# Pallette_v2_1.net
KiCad netlist of a schematic drawn in Altium Designer
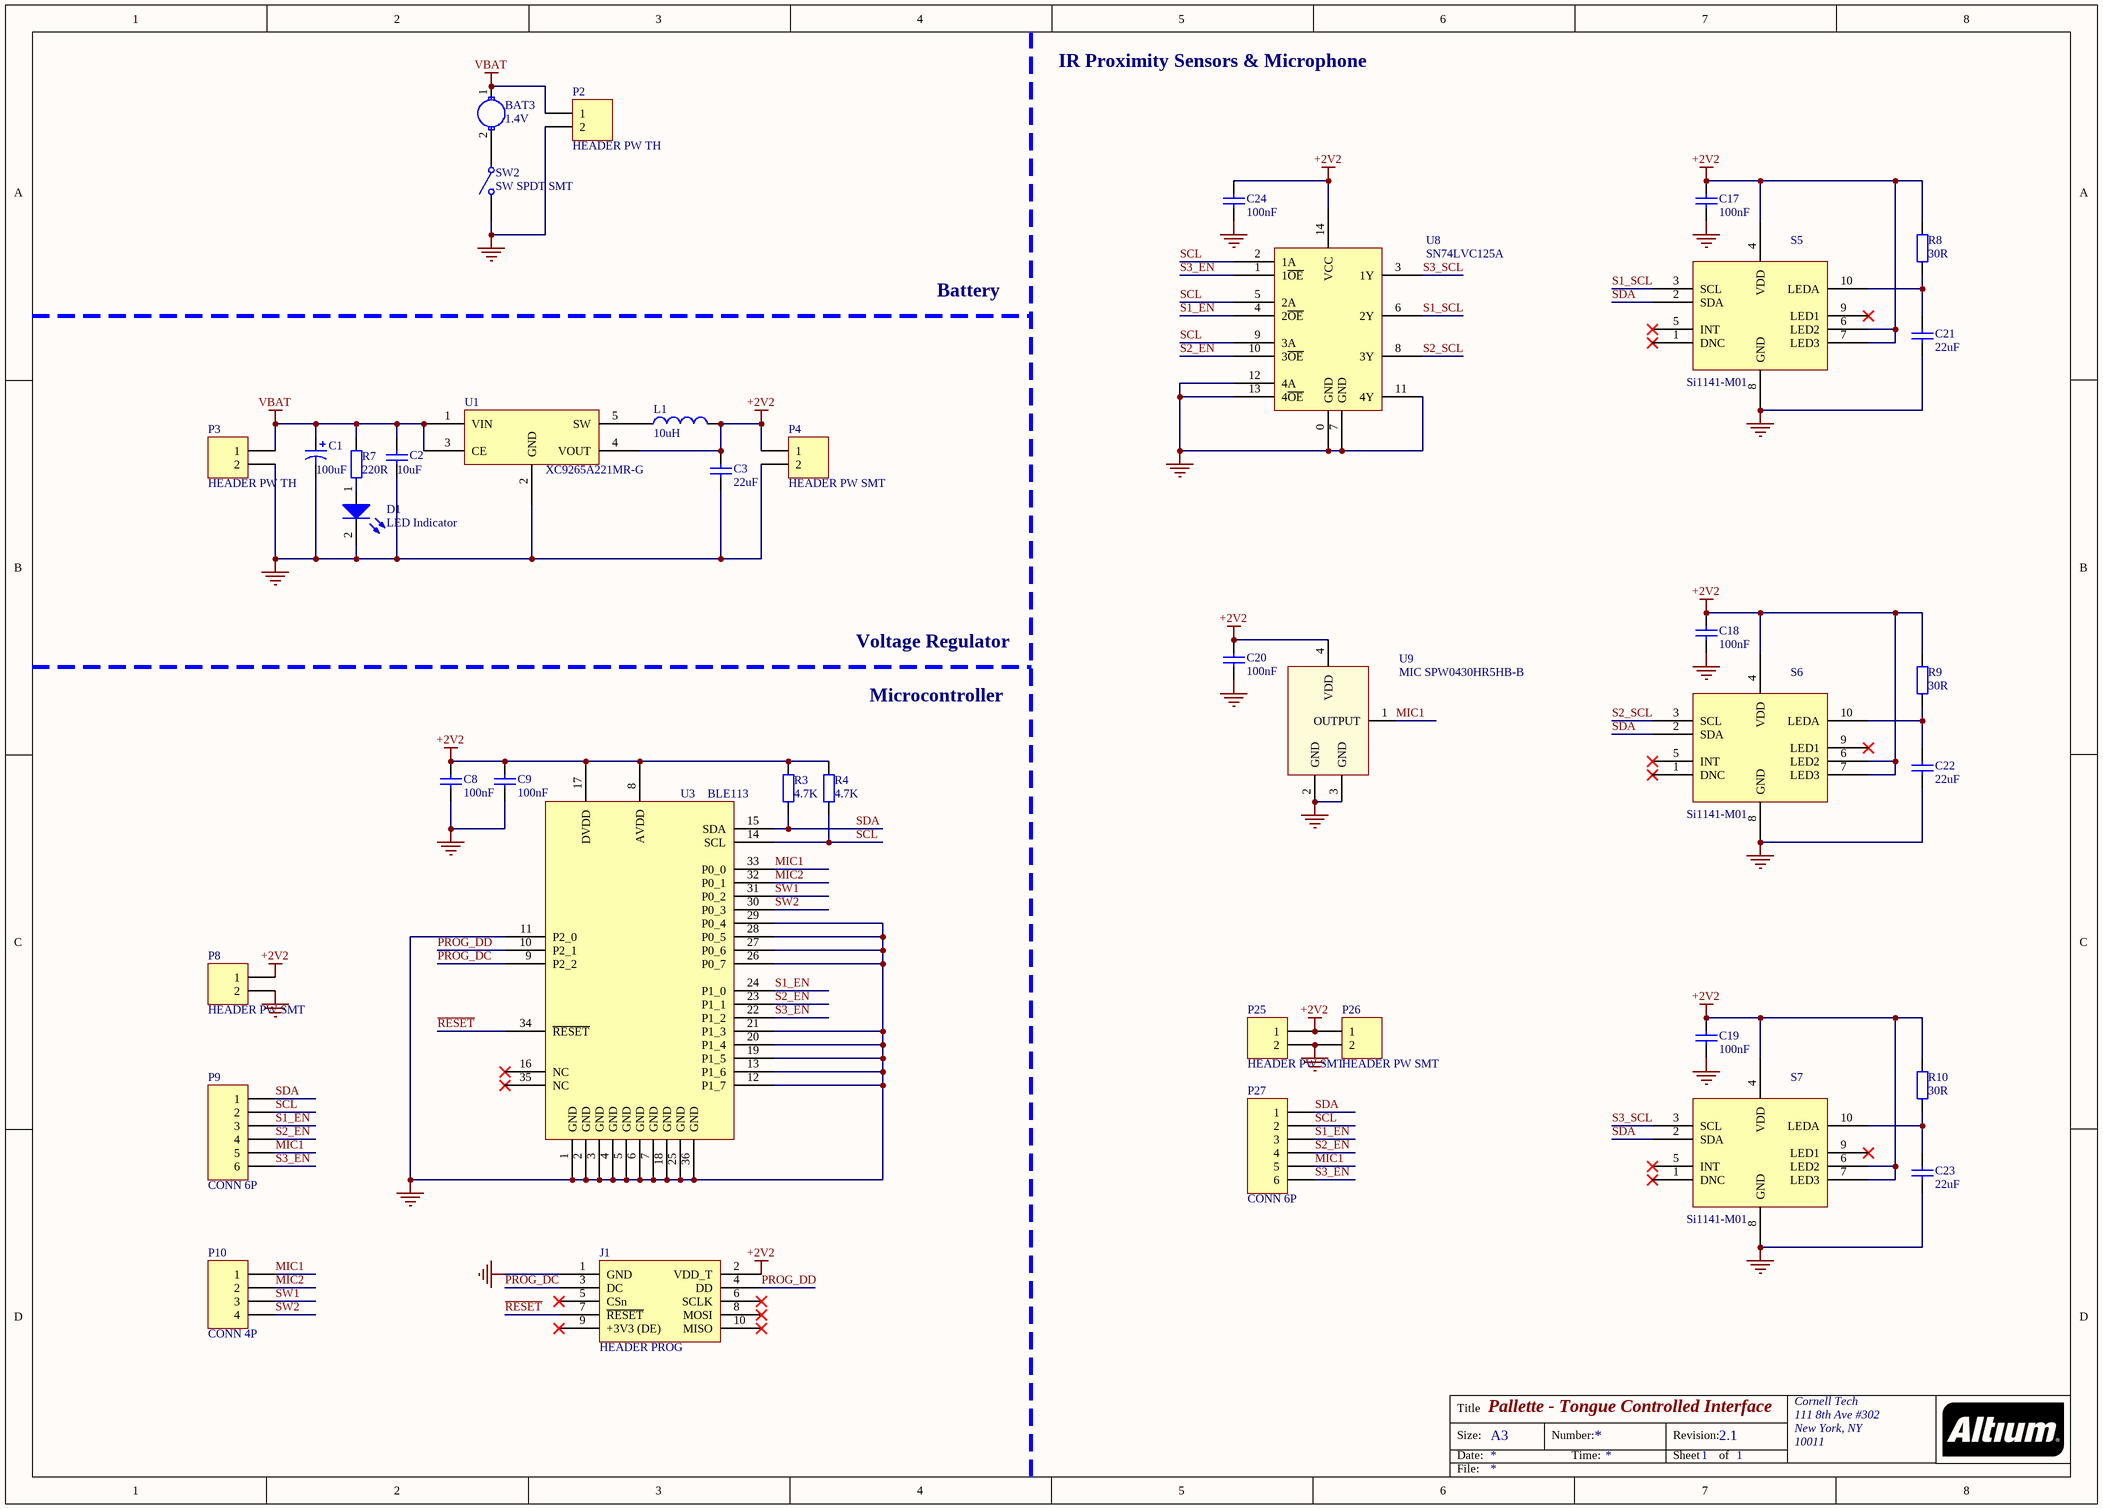
[diagram p0: Pallette v2.1.SchDoc]

(export (version "E")
  (design (tool "Eeschema 10.0.6"))
  (components
    (comp (ref "BAT3")
      (value "1.4V")
      (footprint "BAT RETAINER 13")
      (description "RETAINER COIN CELL SMD 7.9MM")
      (fields
        (field (name "DIGI-KEY PART NUMBER") "36-2988-ND")
        (field (name "MANUFACTURER") "Keystone Electronics")
      )
      (libsource (lib "Schlib") (part "BAT RETAINER 13"))
    )
    (comp (ref "C1")
      (value "100uF")
      (footprint "1411")
      (description "CAP TANT POLY 100UF 8V 1411")
      (fields
        (field (name "DIGI-KEY PART NUMBER") "P16641CT-ND")
        (field (name "MANUFACTURER") "Panasonic Electronic Components")
      )
      (libsource (lib "Schlib") (part "CAP Pol 100uF"))
    )
    (comp (ref "C2")
      (value "10uF")
      (footprint "0603")
      (description "CAP CER 10UF ±20% 10V X5R 0603")
      (fields
        (field (name "DIGI-KEY PART NUMBER") "490-12734-1-ND")
        (field (name "MANUFACTURER PART NUMBER") "GRM188R61A106MAALD")
      )
      (libsource (lib "Schlib") (part "CAP 10uF"))
    )
    (comp (ref "C3")
      (value "22uF")
      (footprint "0603")
      (description "CAP CER 22UF 6.3V X5R 0603")
      (fields
        (field (name "DIGI-KEY PART NUMBER") "490-7611-1-ND")
        (field (name "MANUFACTURER PART NUMBER") "GRM188R60J226MEA0D")
      )
      (libsource (lib "Schlib") (part "CAP 22uF"))
    )
    (comp (ref "C8")
      (value "100nF")
      (footprint "0402")
      (description "CAP CER 0.1UF 10V X5R 0402")
      (fields (field (name "DIGI-KEY PART NUMBER") "490-1318-1-ND") (field (name "MANUFACTURER") "Murata"))
      (libsource (lib "Schlib") (part "CAP 100nF"))
    )
    (comp (ref "C9")
      (value "100nF")
      (footprint "0402")
      (description "CAP CER 0.1UF 10V X5R 0402")
      (fields (field (name "DIGI-KEY PART NUMBER") "490-1318-1-ND") (field (name "MANUFACTURER") "Murata"))
      (libsource (lib "Schlib") (part "CAP 100nF"))
    )
    (comp (ref "C17")
      (value "100nF")
      (footprint "0402")
      (description "CAP CER 0.1UF 10V X5R 0402")
      (fields (field (name "DIGI-KEY PART NUMBER") "490-1318-1-ND") (field (name "MANUFACTURER") "Murata"))
      (libsource (lib "Schlib") (part "CAP 100nF"))
    )
    (comp (ref "C18")
      (value "100nF")
      (footprint "0402")
      (description "CAP CER 0.1UF 10V X5R 0402")
      (fields (field (name "DIGI-KEY PART NUMBER") "490-1318-1-ND") (field (name "MANUFACTURER") "Murata"))
      (libsource (lib "Schlib") (part "CAP 100nF"))
    )
    (comp (ref "C19")
      (value "100nF")
      (footprint "0402")
      (description "CAP CER 0.1UF 10V X5R 0402")
      (fields (field (name "DIGI-KEY PART NUMBER") "490-1318-1-ND") (field (name "MANUFACTURER") "Murata"))
      (libsource (lib "Schlib") (part "CAP 100nF"))
    )
    (comp (ref "C20")
      (value "100nF")
      (footprint "0402")
      (description "CAP CER 0.1UF 10V X5R 0402")
      (fields (field (name "DIGI-KEY PART NUMBER") "490-1318-1-ND") (field (name "MANUFACTURER") "Murata"))
      (libsource (lib "Schlib") (part "CAP 100nF"))
    )
    (comp (ref "C21")
      (value "22uF")
      (footprint "0603")
      (description "CAP CER 22UF 6.3V X5R 0603")
      (fields
        (field (name "DIGI-KEY PART NUMBER") "490-7611-1-ND")
        (field (name "MANUFACTURER PART NUMBER") "GRM188R60J226MEA0D")
      )
      (libsource (lib "Schlib") (part "CAP 22uF"))
    )
    (comp (ref "C22")
      (value "22uF")
      (footprint "0603")
      (description "CAP CER 22UF 6.3V X5R 0603")
      (fields
        (field (name "DIGI-KEY PART NUMBER") "490-7611-1-ND")
        (field (name "MANUFACTURER PART NUMBER") "GRM188R60J226MEA0D")
      )
      (libsource (lib "Schlib") (part "CAP 22uF"))
    )
    (comp (ref "C23")
      (value "22uF")
      (footprint "0603")
      (description "CAP CER 22UF 6.3V X5R 0603")
      (fields
        (field (name "DIGI-KEY PART NUMBER") "490-7611-1-ND")
        (field (name "MANUFACTURER PART NUMBER") "GRM188R60J226MEA0D")
      )
      (libsource (lib "Schlib") (part "CAP 22uF"))
    )
    (comp (ref "C24")
      (value "100nF")
      (footprint "0402")
      (description "CAP CER 0.1UF 10V X5R 0402")
      (fields (field (name "DIGI-KEY PART NUMBER") "490-1318-1-ND") (field (name "MANUFACTURER") "Murata"))
      (libsource (lib "Schlib") (part "CAP 100nF"))
    )
    (comp (ref "D1")
      (value "LED Indicator")
      (footprint "LED")
      (description "LED Red 630nm 2.2V Diffused White Lens 0603")
      (fields
        (field (name "DIGIKEY PART NUMBER") "SML-D12V1WT86CT-ND")
        (field (name "MANUFACTURER PART NUMBER") "SML-D12V1WT86")
      )
      (libsource (lib "Schlib") (part "LED Indicator"))
    )
    (comp (ref "J1")
      (value "HEADER PROG")
      (footprint "TC2050-IDC-NL")
      (description "PADS PROGRAMMING")
      (libsource (lib "Schlib") (part "HEADER PROG"))
    )
    (comp (ref "L1")
      (value "10uH")
      (footprint "0805")
      (description "FIXED IND 10UH 500MA 320 MOHM")
      (fields
        (field (name "DIGI-KEY PART NUMBER") "535-12791-1-ND")
        (field (name "MANUFACTURER") "Abracon LLC")
      )
      (libsource (lib "Schlib") (part "IND 10uH"))
    )
    (comp (ref "P2")
      (value "HEADER PW TH")
      (footprint "PORT PW TH 2P")
      (description "PADS POWER")
      (fields (field (name "PUBLISHER") "Altium Limited"))
      (libsource (lib "Schlib") (part "HEADER PW TH"))
    )
    (comp (ref "P3")
      (value "HEADER PW TH")
      (footprint "PORT PW TH 2P")
      (description "PADS POWER")
      (fields (field (name "PUBLISHER") "Altium Limited"))
      (libsource (lib "") (part "HEADER PW TH_1"))
    )
    (comp (ref "P4")
      (value "HEADER PW SMT")
      (footprint "PORT PW SMT 2P")
      (description "Connection Port")
      (fields (field (name "PUBLISHER") "Altium Limited"))
      (libsource (lib "") (part "HEADER PW SMT_1"))
    )
    (comp (ref "P8")
      (value "HEADER PW SMT")
      (footprint "PORT PW SMT 2P")
      (description "Connection Port")
      (fields (field (name "PUBLISHER") "Altium Limited"))
      (libsource (lib "Schlib") (part "HEADER PW SMT"))
    )
    (comp (ref "P9")
      (value "CONN 6P")
      (footprint "PORT CONN 6P")
      (description "Connection Port")
      (fields (field (name "PUBLISHER") "Altium Limited"))
      (libsource (lib "Schlib") (part "HEADER CONN 6P"))
    )
    (comp (ref "P10")
      (value "CONN 4P")
      (footprint "PORT CONN 4P")
      (description "Connection Port")
      (fields (field (name "PUBLISHER") "Altium Limited"))
      (libsource (lib "Schlib") (part "HEADER CONN 4P"))
    )
    (comp (ref "P25")
      (value "HEADER PW SMT")
      (footprint "PORT PW SMT 2P")
      (description "Connection Port")
      (fields (field (name "PUBLISHER") "Altium Limited"))
      (libsource (lib "Schlib") (part "HEADER PW SMT"))
    )
    (comp (ref "P26")
      (value "HEADER PW SMT")
      (footprint "PORT PW SMT 2P")
      (description "Connection Port")
      (fields (field (name "PUBLISHER") "Altium Limited"))
      (libsource (lib "") (part "HEADER PW SMT_1"))
    )
    (comp (ref "P27")
      (value "CONN 6P")
      (footprint "PORT CONN 6P")
      (description "Connection Port")
      (fields (field (name "PUBLISHER") "Altium Limited"))
      (libsource (lib "Schlib") (part "HEADER CONN 6P"))
    )
    (comp (ref "R3")
      (value "4.7K")
      (footprint "0402")
      (description "RES SMD 4.7K OHM 1% 1/16W 0402")
      (fields (field (name "DIGI-KEY PART NUMBER") "311-4.7KLRCT-ND") (field (name "MANUFACTURER") "Yageo"))
      (libsource (lib "Schlib") (part "RES 4.7K"))
    )
    (comp (ref "R4")
      (value "4.7K")
      (footprint "0402")
      (description "RES SMD 4.7K OHM 1% 1/16W 0402")
      (fields (field (name "DIGI-KEY PART NUMBER") "311-4.7KLRCT-ND") (field (name "MANUFACTURER") "Yageo"))
      (libsource (lib "Schlib") (part "RES 4.7K"))
    )
    (comp (ref "R7")
      (value "220R")
      (footprint "0603")
      (description "RES SMD 220 OHM 1% 1/10W 0603")
      (fields (field (name "DIGI-KEY PART NUMBER") "P220HCT-ND") (field (name "MANUFACTURER") "Panasonic"))
      (libsource (lib "Schlib") (part "RES 220R"))
    )
    (comp (ref "R8")
      (value "30R")
      (footprint "0402")
      (description "RES SMD 30 OHM 1% 1/16W 0402")
      (fields (field (name "DIGI-KEY PART NUMBER") "311-30LRCT-ND") (field (name "MANUFACTURER") "Yageo"))
      (libsource (lib "Schlib") (part "RES 30R"))
    )
    (comp (ref "R9")
      (value "30R")
      (footprint "0402")
      (description "RES SMD 30 OHM 1% 1/16W 0402")
      (fields (field (name "DIGI-KEY PART NUMBER") "311-30LRCT-ND") (field (name "MANUFACTURER") "Yageo"))
      (libsource (lib "Schlib") (part "RES 30R"))
    )
    (comp (ref "R10")
      (value "30R")
      (footprint "0402")
      (description "RES SMD 30 OHM 1% 1/16W 0402")
      (fields (field (name "DIGI-KEY PART NUMBER") "311-30LRCT-ND") (field (name "MANUFACTURER") "Yageo"))
      (libsource (lib "Schlib") (part "RES 30R"))
    )
    (comp (ref "S5")
      (value "Si1141-M01")
      (footprint "SI1141-M01")
      (description "SENS IR PROXIMITY AMB LT 10QFN")
      (fields
        (field (name "DIGI-KEY PART NUMBER") "336-3260-1-ND")
        (field (name "MANUFACTURER") "Silicon Labs")
      )
      (libsource (lib "Schlib") (part "Si1141-M01"))
    )
    (comp (ref "S6")
      (value "Si1141-M01")
      (footprint "SI1141-M01")
      (description "SENS IR PROXIMITY AMB LT 10QFN")
      (fields
        (field (name "DIGI-KEY PART NUMBER") "336-3260-1-ND")
        (field (name "MANUFACTURER") "Silicon Labs")
      )
      (libsource (lib "Schlib") (part "Si1141-M01"))
    )
    (comp (ref "S7")
      (value "Si1141-M01")
      (footprint "SI1141-M01")
      (description "SENS IR PROXIMITY AMB LT 10QFN")
      (fields
        (field (name "DIGI-KEY PART NUMBER") "336-3260-1-ND")
        (field (name "MANUFACTURER") "Silicon Labs")
      )
      (libsource (lib "Schlib") (part "Si1141-M01"))
    )
    (comp (ref "SW2")
      (value "SW SPDT SMT")
      (footprint "SW SPDT SMT")
      (description "SW Single-Pole Double-Throw SMT Right-Angle")
      (fields
        (field (name "DIGIKEY PART NUMBER") "401-2000-ND")
        (field (name "MANUFACTURER") "C&K Components")
      )
      (libsource (lib "Schlib") (part "SW SPDT SMT"))
    )
    (comp (ref "U1")
      (value "XC9265A221MR-G")
      (footprint "SOT-25")
      (description "IC REG BUCK 2.2V 0.2A SYNC SOT25")
      (fields
        (field (name "DIGI-KEY PART NUMBER") "893-1305-1-ND")
        (field (name "MANUFACTURER") "Torex Semiconductor Ltd")
      )
      (libsource (lib "Schlib") (part "VR XC9265A221MR-G"))
    )
    (comp (ref "U3")
      (value "BLE113")
      (footprint "BLE113-A")
      (description "MODULE BT 4.0 BLE113 OTA")
      (fields
        (field (name "MANUFACTURER") "Silicon Labs")
        (field (name "MANUFACTURER PART NUMBER") "BLE113-A-M256K")
      )
      (libsource (lib "Schlib") (part "uC BLE113"))
    )
    (comp (ref "U8")
      (value "SN74LVC125A")
      (footprint "VQFN14")
      (description "IC BUS BUFF TRI-ST QD 14VQFN")
      (fields
        (field (name "MANUFACTURER") "Texas Instruments")
        (field (name "MANUFACTURER PART NUMBER") "SN74LVC125ARGYR")
      )
      (libsource (lib "Schlib") (part "BUFF SN74LVC125A"))
    )
    (comp (ref "U9")
      (value "MIC SPW0430HR5HB-B")
      (footprint "MIC-4P")
      (description "MIC MEMS ANALOG OMNI")
      (fields (field (name "DIGI-KEY PART NUMBER") "423-1215-1-ND") (field (name "MANUFACTURER") "Knowles"))
      (libsource (lib "Schlib") (part "MIC SPW0430HR5HB-B"))
    )
  )
  (nets
    (net (code "1") (name "+2V2") (class "Default")
      (node (ref "C17") (pin "2") (pinfunction "2_2") (pintype "passive"))
      (node (ref "C18") (pin "2") (pinfunction "2_2") (pintype "passive"))
      (node (ref "C19") (pin "2") (pinfunction "2_2") (pintype "passive"))
      (node (ref "C20") (pin "1") (pinfunction "1_1") (pintype "passive"))
      (node (ref "C24") (pin "2") (pinfunction "2_2") (pintype "passive"))
      (node (ref "C3") (pin "2") (pinfunction "2_2") (pintype "passive"))
      (node (ref "C8") (pin "2") (pinfunction "2_2") (pintype "passive"))
      (node (ref "C9") (pin "2") (pinfunction "2_2") (pintype "passive"))
      (node (ref "J1") (pin "2") (pinfunction "VDD_T_2") (pintype "passive"))
      (node (ref "L1") (pin "2") (pinfunction "2_2") (pintype "passive"))
      (node (ref "P25") (pin "1") (pinfunction "1_1") (pintype "passive"))
      (node (ref "P26") (pin "1") (pinfunction "1_1") (pintype "passive"))
      (node (ref "P4") (pin "1") (pinfunction "1_1") (pintype "passive"))
      (node (ref "P8") (pin "1") (pinfunction "1_1") (pintype "passive"))
      (node (ref "R10") (pin "2") (pinfunction "2_2") (pintype "passive"))
      (node (ref "R3") (pin "2") (pinfunction "2_2") (pintype "passive"))
      (node (ref "R4") (pin "2") (pinfunction "2_2") (pintype "passive"))
      (node (ref "R8") (pin "2") (pinfunction "2_2") (pintype "passive"))
      (node (ref "R9") (pin "2") (pinfunction "2_2") (pintype "passive"))
      (node (ref "S5") (pin "4") (pinfunction "VDD_4") (pintype "passive"))
      (node (ref "S5") (pin "6") (pinfunction "LED2_6") (pintype "passive"))
      (node (ref "S5") (pin "7") (pinfunction "LED3_7") (pintype "passive"))
      (node (ref "S6") (pin "4") (pinfunction "VDD_4") (pintype "passive"))
      (node (ref "S6") (pin "6") (pinfunction "LED2_6") (pintype "passive"))
      (node (ref "S6") (pin "7") (pinfunction "LED3_7") (pintype "passive"))
      (node (ref "S7") (pin "4") (pinfunction "VDD_4") (pintype "passive"))
      (node (ref "S7") (pin "6") (pinfunction "LED2_6") (pintype "passive"))
      (node (ref "S7") (pin "7") (pinfunction "LED3_7") (pintype "passive"))
      (node (ref "U1") (pin "4") (pinfunction "VOUT_4") (pintype "passive"))
      (node (ref "U3") (pin "17") (pinfunction "DVDD_17") (pintype "passive"))
      (node (ref "U3") (pin "8") (pinfunction "AVDD_8") (pintype "passive"))
      (node (ref "U8") (pin "14") (pinfunction "VCC_14") (pintype "passive"))
      (node (ref "U9") (pin "4") (pinfunction "VDD_4") (pintype "passive"))
    )
    (net (code "2") (name "/MIC1") (class "Default")
      (node (ref "P10") (pin "1") (pinfunction "1_1") (pintype "passive"))
      (node (ref "P27") (pin "5") (pinfunction "5_5") (pintype "passive"))
      (node (ref "P9") (pin "5") (pinfunction "5_5") (pintype "passive"))
      (node (ref "U3") (pin "33") (pinfunction "P0_0_33") (pintype "passive"))
      (node (ref "U9") (pin "1") (pinfunction "OUTPUT_1") (pintype "passive"))
    )
    (net (code "3") (name "/MIC2") (class "Default")
      (node (ref "P10") (pin "2") (pinfunction "2_2") (pintype "passive"))
      (node (ref "U3") (pin "32") (pinfunction "P0_1_32") (pintype "passive"))
    )
    (net (code "4") (name "/PROG_DC") (class "Default")
      (node (ref "J1") (pin "3") (pinfunction "DC_3") (pintype "passive"))
      (node (ref "U3") (pin "9") (pinfunction "P2_2_9") (pintype "passive"))
    )
    (net (code "5") (name "/PROG_DD") (class "Default")
      (node (ref "J1") (pin "4") (pinfunction "DD_4") (pintype "passive"))
      (node (ref "U3") (pin "10") (pinfunction "P2_1_10") (pintype "passive"))
    )
    (net (code "6") (name "/S1_EN") (class "Default")
      (node (ref "P27") (pin "3") (pinfunction "3_3") (pintype "passive"))
      (node (ref "P9") (pin "3") (pinfunction "3_3") (pintype "passive"))
      (node (ref "U3") (pin "24") (pinfunction "P1_0_24") (pintype "passive"))
      (node (ref "U8") (pin "4") (pinfunction "2~{OE}_4") (pintype "passive"))
    )
    (net (code "7") (name "/S1_SCL") (class "Default")
      (node (ref "S5") (pin "3") (pinfunction "SCL_3") (pintype "passive"))
      (node (ref "U8") (pin "6") (pinfunction "2Y_6") (pintype "passive"))
    )
    (net (code "8") (name "/S2_EN") (class "Default")
      (node (ref "P27") (pin "4") (pinfunction "4_4") (pintype "passive"))
      (node (ref "P9") (pin "4") (pinfunction "4_4") (pintype "passive"))
      (node (ref "U3") (pin "23") (pinfunction "P1_1_23") (pintype "passive"))
      (node (ref "U8") (pin "10") (pinfunction "3~{OE}_10") (pintype "passive"))
    )
    (net (code "9") (name "/S2_SCL") (class "Default")
      (node (ref "S6") (pin "3") (pinfunction "SCL_3") (pintype "passive"))
      (node (ref "U8") (pin "8") (pinfunction "3Y_8") (pintype "passive"))
    )
    (net (code "10") (name "/S3_EN") (class "Default")
      (node (ref "P27") (pin "6") (pinfunction "6_6") (pintype "passive"))
      (node (ref "P9") (pin "6") (pinfunction "6_6") (pintype "passive"))
      (node (ref "U3") (pin "22") (pinfunction "P1_2_22") (pintype "passive"))
      (node (ref "U8") (pin "1") (pinfunction "1~{OE}_1") (pintype "passive"))
    )
    (net (code "11") (name "/S3_SCL") (class "Default")
      (node (ref "S7") (pin "3") (pinfunction "SCL_3") (pintype "passive"))
      (node (ref "U8") (pin "3") (pinfunction "1Y_3") (pintype "passive"))
    )
    (net (code "12") (name "/SCL") (class "Default")
      (node (ref "P27") (pin "2") (pinfunction "2_2") (pintype "passive"))
      (node (ref "P9") (pin "2") (pinfunction "2_2") (pintype "passive"))
      (node (ref "R4") (pin "1") (pinfunction "1_1") (pintype "passive"))
      (node (ref "U3") (pin "14") (pinfunction "SCL_14") (pintype "passive"))
      (node (ref "U8") (pin "2") (pinfunction "1A_2") (pintype "passive"))
      (node (ref "U8") (pin "5") (pinfunction "2A_5") (pintype "passive"))
      (node (ref "U8") (pin "9") (pinfunction "3A_9") (pintype "passive"))
    )
    (net (code "13") (name "/SDA") (class "Default")
      (node (ref "P27") (pin "1") (pinfunction "1_1") (pintype "passive"))
      (node (ref "P9") (pin "1") (pinfunction "1_1") (pintype "passive"))
      (node (ref "R3") (pin "1") (pinfunction "1_1") (pintype "passive"))
      (node (ref "S5") (pin "2") (pinfunction "SDA_2") (pintype "passive"))
      (node (ref "S6") (pin "2") (pinfunction "SDA_2") (pintype "passive"))
      (node (ref "S7") (pin "2") (pinfunction "SDA_2") (pintype "passive"))
      (node (ref "U3") (pin "15") (pinfunction "SDA_15") (pintype "passive"))
    )
    (net (code "14") (name "/SW1") (class "Default")
      (node (ref "P10") (pin "3") (pinfunction "3_3") (pintype "passive"))
      (node (ref "U3") (pin "31") (pinfunction "P0_2_31") (pintype "passive"))
    )
    (net (code "15") (name "/SW2") (class "Default")
      (node (ref "P10") (pin "4") (pinfunction "4_4") (pintype "passive"))
      (node (ref "U3") (pin "30") (pinfunction "P0_3_30") (pintype "passive"))
    )
    (net (code "16") (name "/~{RESET}") (class "Default")
      (node (ref "J1") (pin "7") (pinfunction "~{RESET}_7") (pintype "passive"))
      (node (ref "U3") (pin "34") (pinfunction "~{RESET}_34") (pintype "passive"))
    )
    (net (code "17") (name "GND") (class "Default")
      (node (ref "C1") (pin "2") (pinfunction "2_2") (pintype "passive"))
      (node (ref "C17") (pin "1") (pinfunction "1_1") (pintype "passive"))
      (node (ref "C18") (pin "1") (pinfunction "1_1") (pintype "passive"))
      (node (ref "C19") (pin "1") (pinfunction "1_1") (pintype "passive"))
      (node (ref "C2") (pin "1") (pinfunction "1_1") (pintype "passive"))
      (node (ref "C20") (pin "2") (pinfunction "2_2") (pintype "passive"))
      (node (ref "C21") (pin "1") (pinfunction "1_1") (pintype "passive"))
      (node (ref "C22") (pin "1") (pinfunction "1_1") (pintype "passive"))
      (node (ref "C23") (pin "1") (pinfunction "1_1") (pintype "passive"))
      (node (ref "C24") (pin "1") (pinfunction "1_1") (pintype "passive"))
      (node (ref "C3") (pin "1") (pinfunction "1_1") (pintype "passive"))
      (node (ref "C8") (pin "1") (pinfunction "1_1") (pintype "passive"))
      (node (ref "C9") (pin "1") (pinfunction "1_1") (pintype "passive"))
      (node (ref "D1") (pin "2") (pinfunction "K_2") (pintype "passive"))
      (node (ref "J1") (pin "1") (pinfunction "GND_1") (pintype "passive"))
      (node (ref "P2") (pin "2") (pinfunction "2_2") (pintype "passive"))
      (node (ref "P25") (pin "2") (pinfunction "2_2") (pintype "passive"))
      (node (ref "P26") (pin "2") (pinfunction "2_2") (pintype "passive"))
      (node (ref "P3") (pin "2") (pinfunction "2_2") (pintype "passive"))
      (node (ref "P4") (pin "2") (pinfunction "2_2") (pintype "passive"))
      (node (ref "P8") (pin "2") (pinfunction "2_2") (pintype "passive"))
      (node (ref "S5") (pin "8") (pinfunction "GND_8") (pintype "passive"))
      (node (ref "S6") (pin "8") (pinfunction "GND_8") (pintype "passive"))
      (node (ref "S7") (pin "8") (pinfunction "GND_8") (pintype "passive"))
      (node (ref "SW2") (pin "2") (pinfunction "NO_2") (pintype "passive"))
      (node (ref "U1") (pin "2") (pinfunction "GND_2") (pintype "passive"))
      (node (ref "U3") (pin "1") (pinfunction "GND_1") (pintype "passive"))
      (node (ref "U3") (pin "11") (pinfunction "P2_0_11") (pintype "passive"))
      (node (ref "U3") (pin "12") (pinfunction "P1_7_12") (pintype "passive"))
      (node (ref "U3") (pin "13") (pinfunction "P1_6_13") (pintype "passive"))
      (node (ref "U3") (pin "18") (pinfunction "GND_18") (pintype "passive"))
      (node (ref "U3") (pin "19") (pinfunction "P1_5_19") (pintype "passive"))
      (node (ref "U3") (pin "2") (pinfunction "GND_2") (pintype "passive"))
      (node (ref "U3") (pin "20") (pinfunction "P1_4_20") (pintype "passive"))
      (node (ref "U3") (pin "21") (pinfunction "P1_3_21") (pintype "passive"))
      (node (ref "U3") (pin "25") (pinfunction "GND_25") (pintype "passive"))
      (node (ref "U3") (pin "26") (pinfunction "P0_7_26") (pintype "passive"))
      (node (ref "U3") (pin "27") (pinfunction "P0_6_27") (pintype "passive"))
      (node (ref "U3") (pin "28") (pinfunction "P0_5_28") (pintype "passive"))
      (node (ref "U3") (pin "29") (pinfunction "P0_4_29") (pintype "passive"))
      (node (ref "U3") (pin "3") (pinfunction "GND_3") (pintype "passive"))
      (node (ref "U3") (pin "36") (pinfunction "GND_36") (pintype "passive"))
      (node (ref "U3") (pin "4") (pinfunction "GND_4") (pintype "passive"))
      (node (ref "U3") (pin "5") (pinfunction "GND_5") (pintype "passive"))
      (node (ref "U3") (pin "6") (pinfunction "GND_6") (pintype "passive"))
      (node (ref "U3") (pin "7") (pinfunction "GND_7") (pintype "passive"))
      (node (ref "U8") (pin "0") (pinfunction "GND_0") (pintype "passive"))
      (node (ref "U8") (pin "11") (pinfunction "4Y_11") (pintype "passive"))
      (node (ref "U8") (pin "12") (pinfunction "4A_12") (pintype "passive"))
      (node (ref "U8") (pin "13") (pinfunction "4~{OE}_13") (pintype "passive"))
      (node (ref "U8") (pin "7") (pinfunction "GND_7") (pintype "passive"))
      (node (ref "U9") (pin "2") (pinfunction "GND_2") (pintype "passive"))
      (node (ref "U9") (pin "3") (pinfunction "GND_3") (pintype "passive"))
    )
    (net (code "18") (name "Net-(BAT3--)") (class "Default")
      (node (ref "BAT3") (pin "2") (pinfunction "-_2") (pintype "passive"))
      (node (ref "SW2") (pin "1") (pinfunction "COMMON_1") (pintype "passive"))
    )
    (net (code "19") (name "Net-(D1-A)") (class "Default")
      (node (ref "D1") (pin "1") (pinfunction "A_1") (pintype "passive"))
      (node (ref "R7") (pin "1") (pinfunction "1_1") (pintype "passive"))
    )
    (net (code "20") (name "Net-(S5-LEDA)") (class "Default")
      (node (ref "C21") (pin "2") (pinfunction "2_2") (pintype "passive"))
      (node (ref "R8") (pin "1") (pinfunction "1_1") (pintype "passive"))
      (node (ref "S5") (pin "10") (pinfunction "LEDA_10") (pintype "passive"))
    )
    (net (code "21") (name "Net-(S6-LEDA)") (class "Default")
      (node (ref "C22") (pin "2") (pinfunction "2_2") (pintype "passive"))
      (node (ref "R9") (pin "1") (pinfunction "1_1") (pintype "passive"))
      (node (ref "S6") (pin "10") (pinfunction "LEDA_10") (pintype "passive"))
    )
    (net (code "22") (name "Net-(S7-LEDA)") (class "Default")
      (node (ref "C23") (pin "2") (pinfunction "2_2") (pintype "passive"))
      (node (ref "R10") (pin "1") (pinfunction "1_1") (pintype "passive"))
      (node (ref "S7") (pin "10") (pinfunction "LEDA_10") (pintype "passive"))
    )
    (net (code "23") (name "Net-(U1-SW)") (class "Default")
      (node (ref "L1") (pin "1") (pinfunction "1_1") (pintype "passive"))
      (node (ref "U1") (pin "5") (pinfunction "SW_5") (pintype "passive"))
    )
    (net (code "24") (name "VBAT") (class "Default")
      (node (ref "BAT3") (pin "1") (pinfunction "+_1") (pintype "passive"))
      (node (ref "C1") (pin "1") (pinfunction "1_1") (pintype "passive"))
      (node (ref "C2") (pin "2") (pinfunction "2_2") (pintype "passive"))
      (node (ref "P2") (pin "1") (pinfunction "1_1") (pintype "passive"))
      (node (ref "P3") (pin "1") (pinfunction "1_1") (pintype "passive"))
      (node (ref "R7") (pin "2") (pinfunction "2_2") (pintype "passive"))
      (node (ref "U1") (pin "1") (pinfunction "VIN_1") (pintype "passive"))
      (node (ref "U1") (pin "3") (pinfunction "CE_3") (pintype "passive"))
    )
    (net (code "25") (name "unconnected-(J1-+3V3_(DE)-Pad9)") (class "Default")
      (node (ref "J1") (pin "9") (pinfunction "+3V3_(DE)_9") (pintype "passive+no_connect"))
    )
    (net (code "26") (name "unconnected-(J1-CSn-Pad5)") (class "Default")
      (node (ref "J1") (pin "5") (pinfunction "CSn_5") (pintype "passive+no_connect"))
    )
    (net (code "27") (name "unconnected-(J1-MISO-Pad10)") (class "Default")
      (node (ref "J1") (pin "10") (pinfunction "MISO_10") (pintype "passive+no_connect"))
    )
    (net (code "28") (name "unconnected-(J1-MOSI-Pad8)") (class "Default")
      (node (ref "J1") (pin "8") (pinfunction "MOSI_8") (pintype "passive+no_connect"))
    )
    (net (code "29") (name "unconnected-(J1-SCLK-Pad6)") (class "Default")
      (node (ref "J1") (pin "6") (pinfunction "SCLK_6") (pintype "passive+no_connect"))
    )
    (net (code "30") (name "unconnected-(S5-DNC-Pad1)") (class "Default")
      (node (ref "S5") (pin "1") (pinfunction "DNC_1") (pintype "passive+no_connect"))
    )
    (net (code "31") (name "unconnected-(S5-INT-Pad5)") (class "Default")
      (node (ref "S5") (pin "5") (pinfunction "INT_5") (pintype "passive+no_connect"))
    )
    (net (code "32") (name "unconnected-(S5-LED1-Pad9)") (class "Default")
      (node (ref "S5") (pin "9") (pinfunction "LED1_9") (pintype "passive+no_connect"))
    )
    (net (code "33") (name "unconnected-(S6-DNC-Pad1)") (class "Default")
      (node (ref "S6") (pin "1") (pinfunction "DNC_1") (pintype "passive+no_connect"))
    )
    (net (code "34") (name "unconnected-(S6-INT-Pad5)") (class "Default")
      (node (ref "S6") (pin "5") (pinfunction "INT_5") (pintype "passive+no_connect"))
    )
    (net (code "35") (name "unconnected-(S6-LED1-Pad9)") (class "Default")
      (node (ref "S6") (pin "9") (pinfunction "LED1_9") (pintype "passive+no_connect"))
    )
    (net (code "36") (name "unconnected-(S7-DNC-Pad1)") (class "Default")
      (node (ref "S7") (pin "1") (pinfunction "DNC_1") (pintype "passive+no_connect"))
    )
    (net (code "37") (name "unconnected-(S7-INT-Pad5)") (class "Default")
      (node (ref "S7") (pin "5") (pinfunction "INT_5") (pintype "passive+no_connect"))
    )
    (net (code "38") (name "unconnected-(S7-LED1-Pad9)") (class "Default")
      (node (ref "S7") (pin "9") (pinfunction "LED1_9") (pintype "passive+no_connect"))
    )
    (net (code "39") (name "unconnected-(U3-NC-Pad16)") (class "Default")
      (node (ref "U3") (pin "16") (pinfunction "NC_16") (pintype "passive+no_connect"))
    )
    (net (code "40") (name "unconnected-(U3-NC-Pad35)") (class "Default")
      (node (ref "U3") (pin "35") (pinfunction "NC_35") (pintype "passive+no_connect"))
    )
  )
)
